# Singlepath.net
KiCad netlist of a schematic drawn in Altium Designer
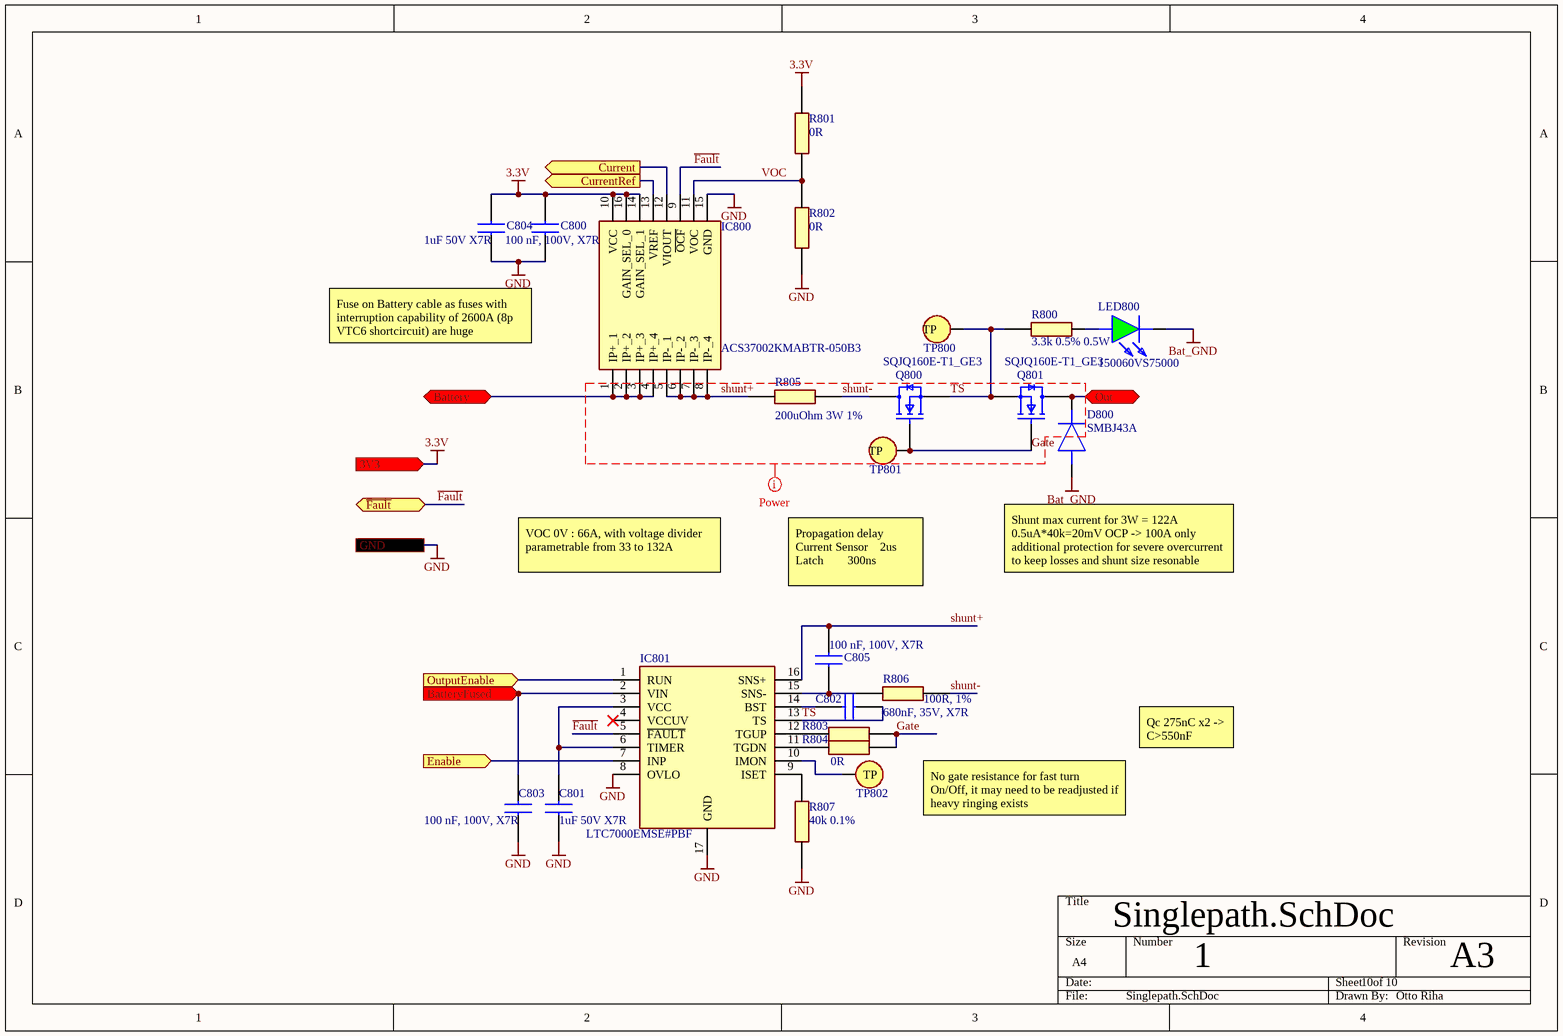
[diagram p0: Singlepath.SchDoc]

(export (version "E")
  (design (tool "Eeschema 10.0.6"))
  (components
    (comp (ref "C800")
      (value "100 nF, 100V, X7R")
      (footprint "SamacSys:MAJx16")
      (description "Capacitor 100nF, 100V, X7R")
      (fields
        (field (name "MANUFACTURER_PART_NUMBER") "MAJCH168BB7104KTEA01")
        (field (name "MOUSER PART NUMBER") "963-MAJCH168BB7104KT")
      )
      (libsource (lib "SamacSys") (part "MAJCH168BB7104KTEA01"))
    )
    (comp (ref "C801")
      (value "1uF 50V X7R")
      (footprint "SamacSys:CAPC1608X90N")
      (description "Capacitor 1uF 50V X7R")
      (fields
        (field (name "MANUFACTURER_PART_NUMBER") "06035C105MAT2A")
        (field (name "MOUSER PART NUMBER") "581-06035C105MAT2A")
      )
      (libsource (lib "SamacSys") (part "06035C105MAT2A"))
    )
    (comp (ref "C802")
      (value "680nF, 35V, X7R")
      (footprint "SamacSys:CAPC1608X90N")
      (description "Capacitor 680nF, 35V, X7R")
      (fields
        (field (name "MANUFACTURER_PART_NUMBER") "CGA3E1X7R1V684K080AC")
        (field (name "MOUSER PART NUMBER") "810-CGA3E1X7R1V684KC")
      )
      (libsource (lib "SamacSys") (part "CGA3E1X7R1V684K080AC"))
    )
    (comp (ref "C803")
      (value "100 nF, 100V, X7R")
      (footprint "SamacSys:MAJx16")
      (description "Capacitor 100nF, 100V, X7R")
      (fields
        (field (name "MANUFACTURER_PART_NUMBER") "MAJCH168BB7104KTEA01")
        (field (name "MOUSER PART NUMBER") "963-MAJCH168BB7104KT")
      )
      (libsource (lib "SamacSys") (part "MAJCH168BB7104KTEA01"))
    )
    (comp (ref "C804")
      (value "1uF 50V X7R")
      (footprint "SamacSys:CAPC1608X90N")
      (description "Capacitor 1uF 50V X7R")
      (fields
        (field (name "MANUFACTURER_PART_NUMBER") "06035C105MAT2A")
        (field (name "MOUSER PART NUMBER") "581-06035C105MAT2A")
      )
      (libsource (lib "SamacSys") (part "06035C105MAT2A"))
    )
    (comp (ref "C805")
      (value "100 nF, 100V, X7R")
      (footprint "SamacSys:MAJx16")
      (description "Capacitor 100nF, 100V, X7R")
      (fields
        (field (name "MANUFACTURER_PART_NUMBER") "MAJCH168BB7104KTEA01")
        (field (name "MOUSER PART NUMBER") "963-MAJCH168BB7104KT")
      )
      (libsource (lib "SamacSys") (part "MAJCH168BB7104KTEA01"))
    )
    (comp (ref "D800")
      (value "SMBJ43A")
      (footprint "SamacSys:DIOM5436X244N")
      (description "Diode")
      (fields (field (name "MOUSER PART NUMBER") "576-SMBJ43A"))
      (libsource (lib "*") (part "SMBJ43A"))
    )
    (comp (ref "IC800")
      (value "ACS37002KMABTR-050B3")
      (footprint "SamacSys:SOIC127P1030X265-16N")
      (description "Integrated Circuit")
      (fields (field (name "MOUSER PART NUMBER") "250-37002KMABTR050B3"))
      (libsource (lib "SamacSys") (part "ACS37002KMABTR-050B3"))
    )
    (comp (ref "IC801")
      (value "LTC7000EMSE#PBF")
      (footprint "SamacSys:SOP50P490X110-17N")
      (description "Integrated Circuit")
      (fields (field (name "MOUSER PART NUMBER") "584-LTC7000EMSEPBF"))
      (libsource (lib "SamacSys") (part "LTC7000EMSE#PBF"))
    )
    (comp (ref "LED800")
      (value "150060VS75000")
      (footprint "SamacSys:LEDC1608X80N")
      (description "LED")
      (fields (field (name "MOUSER PART NUMBER") "710-150060VS75000"))
      (libsource (lib "SamacSys") (part "150060VS75000"))
    )
    (comp (ref "Q800")
      (value "SQJQ160E-T1_GE3")
      (footprint "SamacSys:SQJQ160ET1_GE3")
      (description "MOSFET (N-Channel)")
      (fields (field (name "MOUSER PART NUMBER") "78-SQJQ160E-T1_GE3"))
      (libsource (lib "SamacSys") (part "SQJQ160E-T1_GE3"))
    )
    (comp (ref "Q801")
      (value "SQJQ160E-T1_GE3")
      (footprint "SamacSys:SQJQ160ET1_GE3")
      (description "MOSFET (N-Channel)")
      (fields (field (name "MOUSER PART NUMBER") "78-SQJQ160E-T1_GE3"))
      (libsource (lib "SamacSys") (part "SQJQ160E-T1_GE3"))
    )
    (comp (ref "R800")
      (value "3.3k 0.5% 0.5W")
      (footprint "SamacSys:ERJP06D1000V")
      (description "Resistor")
      (fields
        (field (name "MANUFACTURER_PART_NUMBER") "ERJ-P06J332V")
        (field (name "MOUSER PART NUMBER") "667-ERJ-P06J332V")
      )
      (libsource (lib "*") (part "ERJ-P06J332V"))
    )
    (comp (ref "R801")
      (value "0R")
      (footprint "SamacSys:RESC1608X50N")
      (description "Resistor")
      (fields
        (field (name "MANUFACTURER_PART_NUMBER") "CRCW06030000Z0EC")
        (field (name "MOUSER PART NUMBER") "71-CRCW06030000Z0EC")
      )
      (libsource (lib "SamacSys") (part "CRCW06030000Z0EC"))
    )
    (comp (ref "R802")
      (value "0R")
      (footprint "SamacSys:RESC1608X50N")
      (description "Resistor")
      (fields
        (field (name "MANUFACTURER_PART_NUMBER") "CRCW06030000Z0EC")
        (field (name "MOUSER PART NUMBER") "71-CRCW06030000Z0EC")
      )
      (libsource (lib "SamacSys") (part "CRCW06030000Z0EC"))
    )
    (comp (ref "R803")
      (value "0R")
      (footprint "SamacSys:RESC1608X50N")
      (description "Resistor")
      (fields
        (field (name "MANUFACTURER_PART_NUMBER") "CRCW06030000Z0EC")
        (field (name "MOUSER PART NUMBER") "71-CRCW06030000Z0EC")
      )
      (libsource (lib "") (part "CRCW06030000Z0EC_1"))
    )
    (comp (ref "R804")
      (value "0Ohm")
      (footprint "SamacSys:RESC1608X50N")
      (description "Resistor")
      (fields
        (field (name "MANUFACTURER_PART_NUMBER") "CRCW06030000Z0EC")
        (field (name "MOUSER PART NUMBER") "71-CRCW06030000Z0EC")
      )
      (libsource (lib "") (part "CRCW06030000Z0EC_1"))
    )
    (comp (ref "R805")
      (value "200uOhm 3W 1%")
      (footprint "SamacSys:RESC10052X63N")
      (description "Resistor")
      (fields
        (field (name "MANUFACTURER_PART_NUMBER") "PU3921FKN130U2L")
        (field (name "MOUSER PART NUMBER") "603-PU3921FKN130U2L")
      )
      (libsource (lib "*") (part "PU3921FKN130U2L"))
    )
    (comp (ref "R806")
      (value "100R, 1%")
      (footprint "SamacSys:RESC1608X50N")
      (description "Resistor 100R, 1%")
      (fields
        (field (name "MANUFACTURER_PART_NUMBER") "CRCW0603100RFKEA")
        (field (name "MOUSER PART NUMBER") "71-CRCW0603-100-E3")
      )
      (libsource (lib "SamacSys") (part "CRCW0603100RFKEA"))
    )
    (comp (ref "R807")
      (value "40k 0.1%")
      (footprint "SamacSys:RESC1608X55N")
      (description "Resistor")
      (fields
        (field (name "MANUFACTURER_PART_NUMBER") "AT0603BRD0740KL")
        (field (name "MOUSER PART NUMBER") "603-AT0603BRD0740KL")
      )
      (libsource (lib "*") (part "AT0603BRD0740KL"))
    )
    (comp (ref "TP800")
      (value "Testpoint")
      (footprint "Testpoint")
      (libsource (lib "SamacSys") (part "Testpoint"))
    )
    (comp (ref "TP801")
      (value "Testpoint")
      (footprint "Testpoint")
      (libsource (lib "SamacSys") (part "Testpoint"))
    )
    (comp (ref "TP802")
      (value "Testpoint")
      (footprint "Testpoint")
      (libsource (lib "SamacSys") (part "Testpoint"))
    )
  )
  (nets
    (net (code "1") (name "/Battery") (class "Default")
      (node (ref "IC800") (pin "1") (pinfunction "IP+_1_1") (pintype "passive"))
      (node (ref "IC800") (pin "2") (pinfunction "IP+_2_2") (pintype "passive"))
      (node (ref "IC800") (pin "3") (pinfunction "IP+_3_3") (pintype "passive"))
      (node (ref "IC800") (pin "4") (pinfunction "IP+_4_4") (pintype "passive"))
    )
    (net (code "2") (name "/BatteryFused") (class "Default")
      (node (ref "C803") (pin "2") (pinfunction "2_2") (pintype "passive"))
      (node (ref "IC801") (pin "2") (pinfunction "VIN_2") (pintype "passive"))
    )
    (net (code "3") (name "/Current") (class "Default")
      (node (ref "IC800") (pin "12") (pinfunction "VIOUT_12") (pintype "passive"))
    )
    (net (code "4") (name "/CurrentRef") (class "Default")
      (node (ref "IC800") (pin "13") (pinfunction "VREF_13") (pintype "passive"))
    )
    (net (code "5") (name "/Enable") (class "Default")
      (node (ref "IC801") (pin "7") (pinfunction "INP_7") (pintype "passive"))
    )
    (net (code "6") (name "/Gate") (class "Default")
      (node (ref "Q800") (pin "1") (pinfunction "G_1") (pintype "passive"))
      (node (ref "Q801") (pin "1") (pinfunction "G_1") (pintype "passive"))
      (node (ref "R803") (pin "2") (pinfunction "2_2") (pintype "passive"))
      (node (ref "R804") (pin "2") (pinfunction "2_2") (pintype "passive"))
      (node (ref "TP801") (pin "1") (pinfunction "TP_1") (pintype "passive"))
    )
    (net (code "7") (name "/Out") (class "Default")
      (node (ref "D800") (pin "1") (pinfunction "K_1") (pintype "passive"))
      (node (ref "Q801") (pin "3") (pinfunction "D_1_3") (pintype "passive"))
    )
    (net (code "8") (name "/OutputEnable") (class "Default")
      (node (ref "IC801") (pin "1") (pinfunction "RUN_1") (pintype "passive"))
    )
    (net (code "9") (name "/TS") (class "Default")
      (node (ref "C802") (pin "2") (pinfunction "2_2") (pintype "passive"))
      (node (ref "IC801") (pin "13") (pinfunction "TS_13") (pintype "passive"))
      (node (ref "Q800") (pin "2") (pinfunction "S_1_2") (pintype "passive"))
      (node (ref "Q801") (pin "2") (pinfunction "S_1_2") (pintype "passive"))
      (node (ref "R800") (pin "1") (pinfunction "1_1") (pintype "passive"))
      (node (ref "TP800") (pin "1") (pinfunction "TP_1") (pintype "passive"))
    )
    (net (code "10") (name "/VOC") (class "Default")
      (node (ref "IC800") (pin "11") (pinfunction "VOC_11") (pintype "passive"))
      (node (ref "R801") (pin "1") (pinfunction "1_1") (pintype "passive"))
      (node (ref "R802") (pin "2") (pinfunction "2_2") (pintype "passive"))
    )
    (net (code "11") (name "/shunt+") (class "Default")
      (node (ref "C805") (pin "2") (pinfunction "2_2") (pintype "passive"))
      (node (ref "IC800") (pin "5") (pinfunction "IP-_1_5") (pintype "passive"))
      (node (ref "IC800") (pin "6") (pinfunction "IP-_2_6") (pintype "passive"))
      (node (ref "IC800") (pin "7") (pinfunction "IP-_3_7") (pintype "passive"))
      (node (ref "IC800") (pin "8") (pinfunction "IP-_4_8") (pintype "passive"))
      (node (ref "IC801") (pin "16") (pinfunction "SNS+_16") (pintype "passive"))
      (node (ref "R805") (pin "1") (pinfunction "1_1") (pintype "passive"))
    )
    (net (code "12") (name "/shunt-") (class "Default")
      (node (ref "Q800") (pin "3") (pinfunction "D_1_3") (pintype "passive"))
      (node (ref "R805") (pin "2") (pinfunction "2_2") (pintype "passive"))
      (node (ref "R806") (pin "2") (pinfunction "2_2") (pintype "passive"))
    )
    (net (code "13") (name "/~{Fault}") (class "Default")
      (node (ref "IC800") (pin "9") (pinfunction "~{OCF}_9") (pintype "passive"))
      (node (ref "IC801") (pin "5") (pinfunction "~{FAULT}_5") (pintype "passive"))
    )
    (net (code "14") (name "3.3V") (class "Default")
      (node (ref "C800") (pin "2") (pinfunction "2_2") (pintype "passive"))
      (node (ref "C804") (pin "2") (pinfunction "2_2") (pintype "passive"))
      (node (ref "IC800") (pin "10") (pinfunction "VCC_10") (pintype "passive"))
      (node (ref "IC800") (pin "14") (pinfunction "GAIN_SEL_1_14") (pintype "passive"))
      (node (ref "IC800") (pin "16") (pinfunction "GAIN_SEL_0_16") (pintype "passive"))
      (node (ref "R801") (pin "2") (pinfunction "2_2") (pintype "passive"))
    )
    (net (code "15") (name "Bat_GND") (class "Default")
      (node (ref "D800") (pin "2") (pinfunction "A_2") (pintype "passive"))
      (node (ref "LED800") (pin "1") (pinfunction "K_1") (pintype "passive"))
    )
    (net (code "16") (name "GND") (class "Default")
      (node (ref "C800") (pin "1") (pinfunction "1_1") (pintype "passive"))
      (node (ref "C801") (pin "1") (pinfunction "1_1") (pintype "passive"))
      (node (ref "C803") (pin "1") (pinfunction "1_1") (pintype "passive"))
      (node (ref "C804") (pin "1") (pinfunction "1_1") (pintype "passive"))
      (node (ref "IC800") (pin "15") (pinfunction "GND_15") (pintype "passive"))
      (node (ref "IC801") (pin "17") (pinfunction "GND_17") (pintype "passive"))
      (node (ref "IC801") (pin "8") (pinfunction "OVLO_8") (pintype "passive"))
      (node (ref "R802") (pin "1") (pinfunction "1_1") (pintype "passive"))
      (node (ref "R807") (pin "1") (pinfunction "1_1") (pintype "passive"))
    )
    (net (code "17") (name "Net-(IC801-BST)") (class "Default")
      (node (ref "C802") (pin "1") (pinfunction "1_1") (pintype "passive"))
      (node (ref "IC801") (pin "14") (pinfunction "BST_14") (pintype "passive"))
    )
    (net (code "18") (name "Net-(IC801-IMON)") (class "Default")
      (node (ref "IC801") (pin "10") (pinfunction "IMON_10") (pintype "passive"))
      (node (ref "TP802") (pin "1") (pinfunction "TP_1") (pintype "passive"))
    )
    (net (code "19") (name "Net-(IC801-ISET)") (class "Default")
      (node (ref "IC801") (pin "9") (pinfunction "ISET_9") (pintype "passive"))
      (node (ref "R807") (pin "2") (pinfunction "2_2") (pintype "passive"))
    )
    (net (code "20") (name "Net-(IC801-SNS-)") (class "Default")
      (node (ref "C805") (pin "1") (pinfunction "1_1") (pintype "passive"))
      (node (ref "IC801") (pin "15") (pinfunction "SNS-_15") (pintype "passive"))
      (node (ref "R806") (pin "1") (pinfunction "1_1") (pintype "passive"))
    )
    (net (code "21") (name "Net-(IC801-TGDN)") (class "Default")
      (node (ref "IC801") (pin "11") (pinfunction "TGDN_11") (pintype "passive"))
      (node (ref "R804") (pin "1") (pinfunction "1_1") (pintype "passive"))
    )
    (net (code "22") (name "Net-(IC801-TGUP)") (class "Default")
      (node (ref "IC801") (pin "12") (pinfunction "TGUP_12") (pintype "passive"))
      (node (ref "R803") (pin "1") (pinfunction "1_1") (pintype "passive"))
    )
    (net (code "23") (name "Net-(IC801-TIMER)") (class "Default")
      (node (ref "C801") (pin "2") (pinfunction "2_2") (pintype "passive"))
      (node (ref "IC801") (pin "3") (pinfunction "VCC_3") (pintype "passive"))
      (node (ref "IC801") (pin "6") (pinfunction "TIMER_6") (pintype "passive"))
    )
    (net (code "24") (name "Net-(LED800-A)") (class "Default")
      (node (ref "LED800") (pin "2") (pinfunction "A_2") (pintype "passive"))
      (node (ref "R800") (pin "2") (pinfunction "2_2") (pintype "passive"))
    )
    (net (code "25") (name "unconnected-(IC801-VCCUV-Pad4)") (class "Default")
      (node (ref "IC801") (pin "4") (pinfunction "VCCUV_4") (pintype "passive+no_connect"))
    )
  )
)
